# csi_cam.net
KiCad netlist of a schematic drawn in Altium Designer
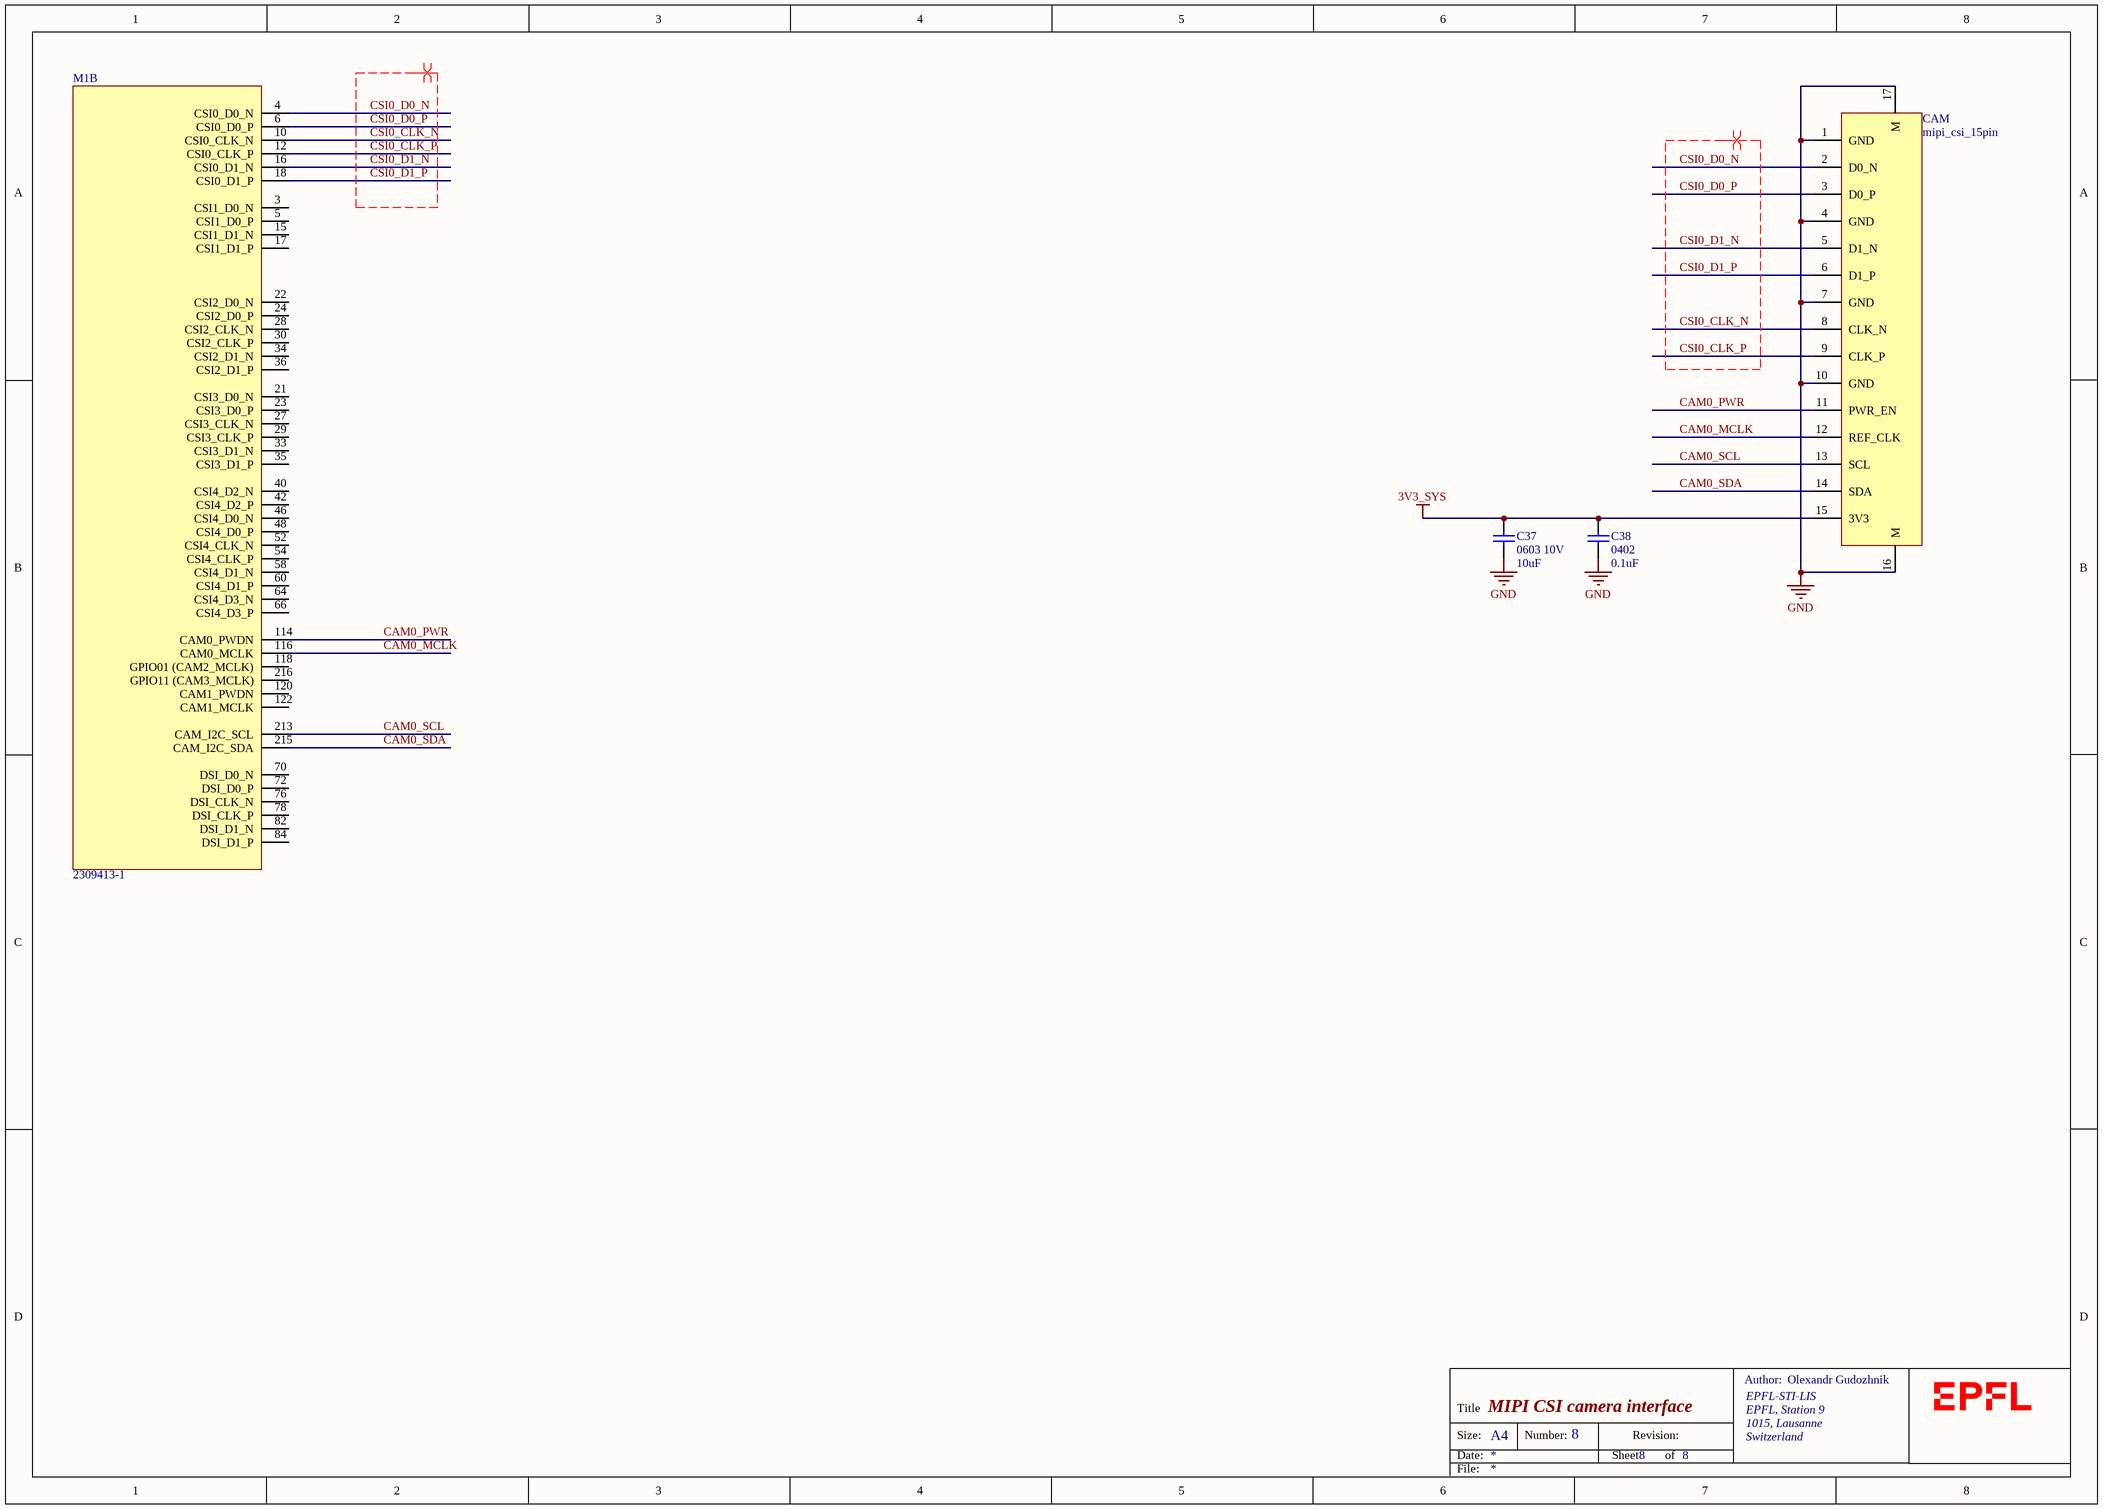
[diagram p0: csi_cam.SchDoc]

(export (version "E")
  (design (tool "Eeschema 10.0.6"))
  (components
    (comp (ref "C37")
      (value "0603 10V")
      (footprint "cap0603")
      (description "standard, non-polarized capacitor")
      (fields (field (name "ALTIUM_VALUE") "10uF"))
      (libsource (lib "capacitor") (part "cap"))
    )
    (comp (ref "C38")
      (value "0402")
      (footprint "cap0402")
      (description "standard, non-polarized capacitor")
      (fields (field (name "ALTIUM_VALUE") "0.1uF"))
      (libsource (lib "capacitor") (part "cap"))
    )
    (comp (ref "CAM")
      (value "mipi_csi_15pin")
      (footprint "molex_52271_15pin")
      (description "15 pin FPC connector")
      (libsource (lib "connector") (part "mipi_csi_15pin"))
    )
    (comp (ref "M1")
      (value "2309413-1")
      (footprint "jetson-nano-connector")
      (description "Memory Socket, DDR4, SODIMM Socket, 260 Contacts, Copper Alloy, Gold Plated Contacts")
      (fields (field (name "MANUFACTURER") "TE CONNECTIVITY"))
      (libsource (lib "jetson-nano-baseboard") (part "2309413-1"))
    )
  )
  (nets
    (net (code "1") (name "/CAM0_MCLK") (class "Default")
      (node (ref "CAM") (pin "12") (pinfunction "REF_CLK_12") (pintype "passive"))
      (node (ref "M1") (pin "116") (pinfunction "CAM0_MCLK_116") (pintype "passive"))
    )
    (net (code "2") (name "/CAM0_PWR") (class "Default")
      (node (ref "CAM") (pin "11") (pinfunction "PWR_EN_11") (pintype "passive"))
      (node (ref "M1") (pin "114") (pinfunction "CAM0_PWDN_114") (pintype "passive"))
    )
    (net (code "3") (name "/CAM0_SCL") (class "Default")
      (node (ref "CAM") (pin "13") (pinfunction "SCL_13") (pintype "passive"))
      (node (ref "M1") (pin "213") (pinfunction "CAM_I2C_SCL_213") (pintype "passive"))
    )
    (net (code "4") (name "/CAM0_SDA") (class "Default")
      (node (ref "CAM") (pin "14") (pinfunction "SDA_14") (pintype "passive"))
      (node (ref "M1") (pin "215") (pinfunction "CAM_I2C_SDA_215") (pintype "passive"))
    )
    (net (code "5") (name "/CSI0_CLK_N") (class "Default")
      (node (ref "CAM") (pin "8") (pinfunction "CLK_N_8") (pintype "passive"))
      (node (ref "M1") (pin "10") (pinfunction "CSI0_CLK_N_10") (pintype "passive"))
    )
    (net (code "6") (name "/CSI0_CLK_P") (class "Default")
      (node (ref "CAM") (pin "9") (pinfunction "CLK_P_9") (pintype "passive"))
      (node (ref "M1") (pin "12") (pinfunction "CSI0_CLK_P_12") (pintype "passive"))
    )
    (net (code "7") (name "/CSI0_D0_N") (class "Default")
      (node (ref "CAM") (pin "2") (pinfunction "D0_N_2") (pintype "passive"))
      (node (ref "M1") (pin "4") (pinfunction "CSI0_D0_N_4") (pintype "passive"))
    )
    (net (code "8") (name "/CSI0_D0_P") (class "Default")
      (node (ref "CAM") (pin "3") (pinfunction "D0_P_3") (pintype "passive"))
      (node (ref "M1") (pin "6") (pinfunction "CSI0_D0_P_6") (pintype "passive"))
    )
    (net (code "9") (name "/CSI0_D1_N") (class "Default")
      (node (ref "CAM") (pin "5") (pinfunction "D1_N_5") (pintype "passive"))
      (node (ref "M1") (pin "16") (pinfunction "CSI0_D1_N_16") (pintype "passive"))
    )
    (net (code "10") (name "/CSI0_D1_P") (class "Default")
      (node (ref "CAM") (pin "6") (pinfunction "D1_P_6") (pintype "passive"))
      (node (ref "M1") (pin "18") (pinfunction "CSI0_D1_P_18") (pintype "passive"))
    )
    (net (code "11") (name "3V3_SYS") (class "Default")
      (node (ref "C37") (pin "2") (pinfunction "2_2") (pintype "passive"))
      (node (ref "C38") (pin "1") (pinfunction "1_1") (pintype "passive"))
      (node (ref "CAM") (pin "15") (pinfunction "3V3_15") (pintype "passive"))
    )
    (net (code "12") (name "GND") (class "Default")
      (node (ref "C37") (pin "1") (pinfunction "1_1") (pintype "passive"))
      (node (ref "C38") (pin "2") (pinfunction "2_2") (pintype "passive"))
      (node (ref "CAM") (pin "1") (pinfunction "GND_1") (pintype "passive"))
      (node (ref "CAM") (pin "10") (pinfunction "GND_10") (pintype "passive"))
      (node (ref "CAM") (pin "16") (pinfunction "M_16") (pintype "passive"))
      (node (ref "CAM") (pin "17") (pinfunction "M_17") (pintype "passive"))
      (node (ref "CAM") (pin "4") (pinfunction "GND_4") (pintype "passive"))
      (node (ref "CAM") (pin "7") (pinfunction "GND_7") (pintype "passive"))
    )
    (net (code "13") (name "unconnected-(M1B-CAM1_MCLK-Pad122)") (class "Default")
      (node (ref "M1") (pin "122") (pinfunction "CAM1_MCLK_122") (pintype "passive"))
    )
    (net (code "14") (name "unconnected-(M1B-CAM1_PWDN-Pad120)") (class "Default")
      (node (ref "M1") (pin "120") (pinfunction "CAM1_PWDN_120") (pintype "passive"))
    )
    (net (code "15") (name "unconnected-(M1B-CSI1_D0_N-Pad3)") (class "Default")
      (node (ref "M1") (pin "3") (pinfunction "CSI1_D0_N_3") (pintype "passive"))
    )
    (net (code "16") (name "unconnected-(M1B-CSI1_D0_P-Pad5)") (class "Default")
      (node (ref "M1") (pin "5") (pinfunction "CSI1_D0_P_5") (pintype "passive"))
    )
    (net (code "17") (name "unconnected-(M1B-CSI1_D1_N-Pad15)") (class "Default")
      (node (ref "M1") (pin "15") (pinfunction "CSI1_D1_N_15") (pintype "passive"))
    )
    (net (code "18") (name "unconnected-(M1B-CSI1_D1_P-Pad17)") (class "Default")
      (node (ref "M1") (pin "17") (pinfunction "CSI1_D1_P_17") (pintype "passive"))
    )
    (net (code "19") (name "unconnected-(M1B-CSI2_CLK_N-Pad28)") (class "Default")
      (node (ref "M1") (pin "28") (pinfunction "CSI2_CLK_N_28") (pintype "passive"))
    )
    (net (code "20") (name "unconnected-(M1B-CSI2_CLK_P-Pad30)") (class "Default")
      (node (ref "M1") (pin "30") (pinfunction "CSI2_CLK_P_30") (pintype "passive"))
    )
    (net (code "21") (name "unconnected-(M1B-CSI2_D0_N-Pad22)") (class "Default")
      (node (ref "M1") (pin "22") (pinfunction "CSI2_D0_N_22") (pintype "passive"))
    )
    (net (code "22") (name "unconnected-(M1B-CSI2_D0_P-Pad24)") (class "Default")
      (node (ref "M1") (pin "24") (pinfunction "CSI2_D0_P_24") (pintype "passive"))
    )
    (net (code "23") (name "unconnected-(M1B-CSI2_D1_N-Pad34)") (class "Default")
      (node (ref "M1") (pin "34") (pinfunction "CSI2_D1_N_34") (pintype "passive"))
    )
    (net (code "24") (name "unconnected-(M1B-CSI2_D1_P-Pad36)") (class "Default")
      (node (ref "M1") (pin "36") (pinfunction "CSI2_D1_P_36") (pintype "passive"))
    )
    (net (code "25") (name "unconnected-(M1B-CSI3_CLK_N-Pad27)") (class "Default")
      (node (ref "M1") (pin "27") (pinfunction "CSI3_CLK_N_27") (pintype "passive"))
    )
    (net (code "26") (name "unconnected-(M1B-CSI3_CLK_P-Pad29)") (class "Default")
      (node (ref "M1") (pin "29") (pinfunction "CSI3_CLK_P_29") (pintype "passive"))
    )
    (net (code "27") (name "unconnected-(M1B-CSI3_D0_N-Pad21)") (class "Default")
      (node (ref "M1") (pin "21") (pinfunction "CSI3_D0_N_21") (pintype "passive"))
    )
    (net (code "28") (name "unconnected-(M1B-CSI3_D0_P-Pad23)") (class "Default")
      (node (ref "M1") (pin "23") (pinfunction "CSI3_D0_P_23") (pintype "passive"))
    )
    (net (code "29") (name "unconnected-(M1B-CSI3_D1_N-Pad33)") (class "Default")
      (node (ref "M1") (pin "33") (pinfunction "CSI3_D1_N_33") (pintype "passive"))
    )
    (net (code "30") (name "unconnected-(M1B-CSI3_D1_P-Pad35)") (class "Default")
      (node (ref "M1") (pin "35") (pinfunction "CSI3_D1_P_35") (pintype "passive"))
    )
    (net (code "31") (name "unconnected-(M1B-CSI4_CLK_N-Pad52)") (class "Default")
      (node (ref "M1") (pin "52") (pinfunction "CSI4_CLK_N_52") (pintype "passive"))
    )
    (net (code "32") (name "unconnected-(M1B-CSI4_CLK_P-Pad54)") (class "Default")
      (node (ref "M1") (pin "54") (pinfunction "CSI4_CLK_P_54") (pintype "passive"))
    )
    (net (code "33") (name "unconnected-(M1B-CSI4_D0_N-Pad46)") (class "Default")
      (node (ref "M1") (pin "46") (pinfunction "CSI4_D0_N_46") (pintype "passive"))
    )
    (net (code "34") (name "unconnected-(M1B-CSI4_D0_P-Pad48)") (class "Default")
      (node (ref "M1") (pin "48") (pinfunction "CSI4_D0_P_48") (pintype "passive"))
    )
    (net (code "35") (name "unconnected-(M1B-CSI4_D1_N-Pad58)") (class "Default")
      (node (ref "M1") (pin "58") (pinfunction "CSI4_D1_N_58") (pintype "passive"))
    )
    (net (code "36") (name "unconnected-(M1B-CSI4_D1_P-Pad60)") (class "Default")
      (node (ref "M1") (pin "60") (pinfunction "CSI4_D1_P_60") (pintype "passive"))
    )
    (net (code "37") (name "unconnected-(M1B-CSI4_D2_N-Pad40)") (class "Default")
      (node (ref "M1") (pin "40") (pinfunction "CSI4_D2_N_40") (pintype "passive"))
    )
    (net (code "38") (name "unconnected-(M1B-CSI4_D2_P-Pad42)") (class "Default")
      (node (ref "M1") (pin "42") (pinfunction "CSI4_D2_P_42") (pintype "passive"))
    )
    (net (code "39") (name "unconnected-(M1B-CSI4_D3_N-Pad64)") (class "Default")
      (node (ref "M1") (pin "64") (pinfunction "CSI4_D3_N_64") (pintype "passive"))
    )
    (net (code "40") (name "unconnected-(M1B-CSI4_D3_P-Pad66)") (class "Default")
      (node (ref "M1") (pin "66") (pinfunction "CSI4_D3_P_66") (pintype "passive"))
    )
    (net (code "41") (name "unconnected-(M1B-DSI_CLK_N-Pad76)") (class "Default")
      (node (ref "M1") (pin "76") (pinfunction "DSI_CLK_N_76") (pintype "passive"))
    )
    (net (code "42") (name "unconnected-(M1B-DSI_CLK_P-Pad78)") (class "Default")
      (node (ref "M1") (pin "78") (pinfunction "DSI_CLK_P_78") (pintype "passive"))
    )
    (net (code "43") (name "unconnected-(M1B-DSI_D0_N-Pad70)") (class "Default")
      (node (ref "M1") (pin "70") (pinfunction "DSI_D0_N_70") (pintype "passive"))
    )
    (net (code "44") (name "unconnected-(M1B-DSI_D0_P-Pad72)") (class "Default")
      (node (ref "M1") (pin "72") (pinfunction "DSI_D0_P_72") (pintype "passive"))
    )
    (net (code "45") (name "unconnected-(M1B-DSI_D1_N-Pad82)") (class "Default")
      (node (ref "M1") (pin "82") (pinfunction "DSI_D1_N_82") (pintype "passive"))
    )
    (net (code "46") (name "unconnected-(M1B-DSI_D1_P-Pad84)") (class "Default")
      (node (ref "M1") (pin "84") (pinfunction "DSI_D1_P_84") (pintype "passive"))
    )
    (net (code "47") (name "unconnected-(M1B-GPIO01_(CAM2_MCLK)-Pad118)") (class "Default")
      (node (ref "M1") (pin "118") (pinfunction "GPIO01_(CAM2_MCLK)_118") (pintype "passive"))
    )
    (net (code "48") (name "unconnected-(M1B-GPIO11_(CAM3_MCLK)-Pad216)") (class "Default")
      (node (ref "M1") (pin "216") (pinfunction "GPIO11_(CAM3_MCLK)_216") (pintype "passive"))
    )
  )
)
